# Mainboard_MCU_Func.net
KiCad netlist of a schematic drawn in Altium Designer
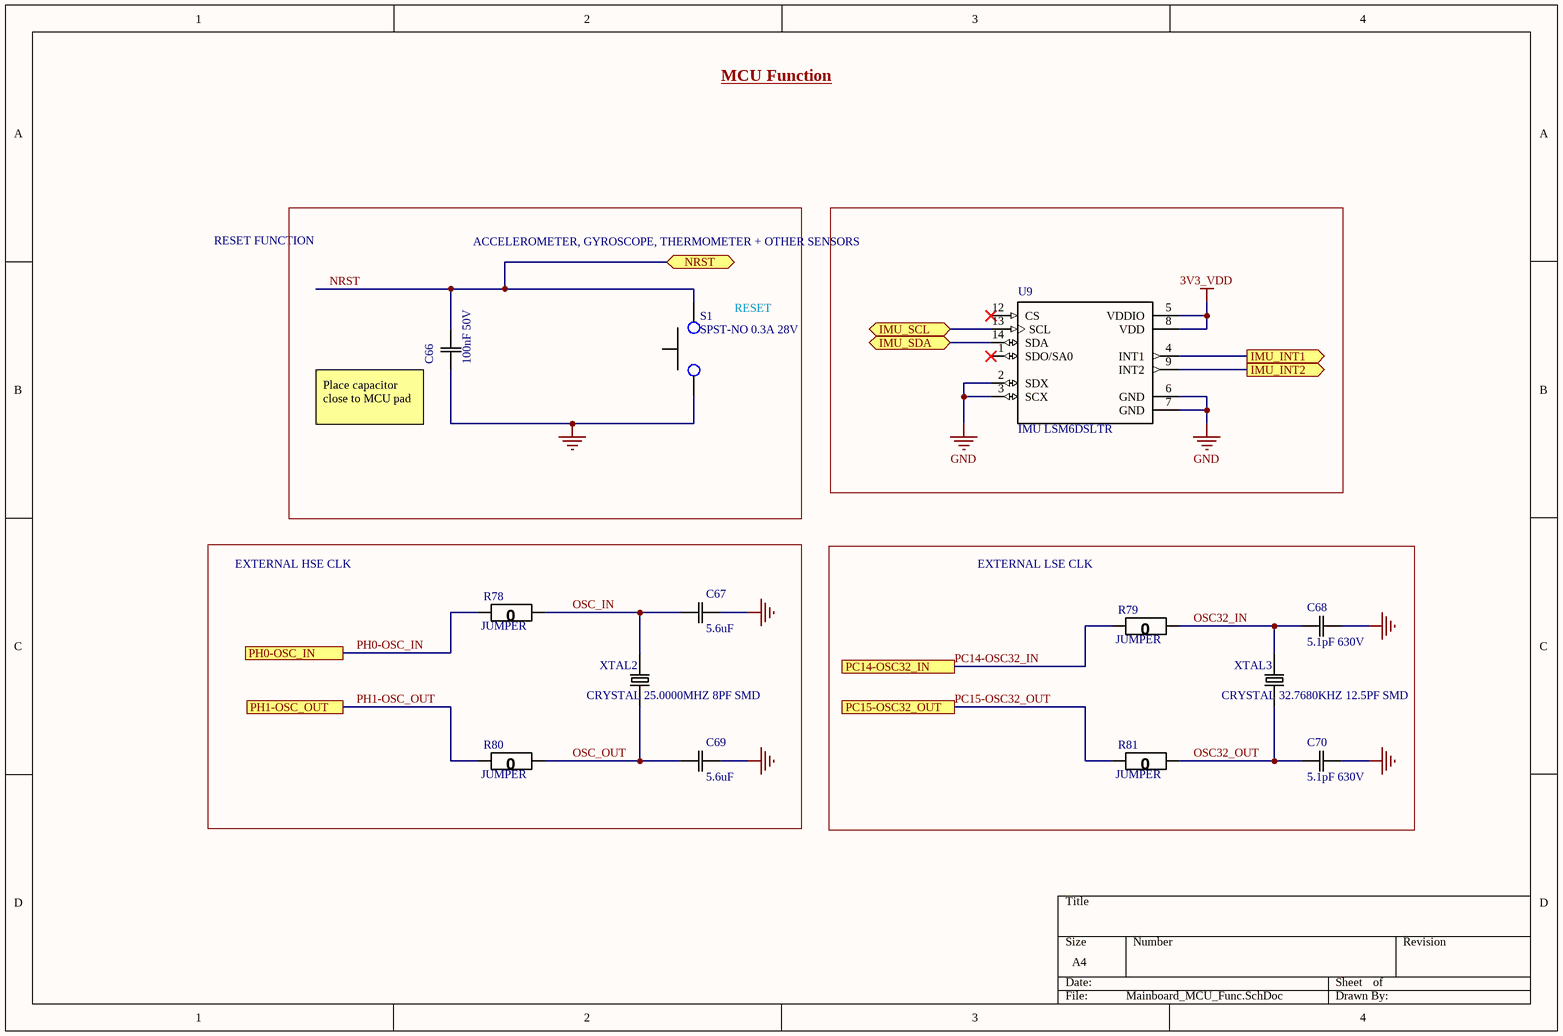
[diagram p0: Mainboard_MCU_Func.SchDoc]

(export (version "E")
  (design (tool "Eeschema 10.0.6"))
  (components
    (comp (ref "C66")
      (value "100nF 50V")
      (footprint "0805")
      (description "CAP CER 0.1UF 50V X7R 0805")
      (fields (field (name "TOLERANCE") "10%"))
      (libsource (lib "AltiumLibraries") (part "CAP 100nF 50V"))
    )
    (comp (ref "C67")
      (value "5.6uF")
      (footprint "0805")
      (description "CAP CER 5.6UF 6.3V X5R 0805")
      (fields (field (name "TOLERANCE") "10%"))
      (libsource (lib "AltiumLibraries") (part "CAP 5.6uF 6.3V"))
    )
    (comp (ref "C68")
      (value "5.1pF 630V")
      (footprint "0805")
      (description "CAP CER 5.1PF 630V C0G/NP0 0805")
      (fields (field (name "TOLERANCE") "10%"))
      (libsource (lib "AltiumLibraries") (part "CAP 5.1pF 630V"))
    )
    (comp (ref "C69")
      (value "5.6uF")
      (footprint "0805")
      (description "CAP CER 5.6UF 6.3V X5R 0805")
      (fields (field (name "TOLERANCE") "10%"))
      (libsource (lib "AltiumLibraries") (part "CAP 5.6uF 6.3V"))
    )
    (comp (ref "C70")
      (value "5.1pF 630V")
      (footprint "0805")
      (description "CAP CER 5.1PF 630V C0G/NP0 0805")
      (fields (field (name "TOLERANCE") "10%"))
      (libsource (lib "AltiumLibraries") (part "CAP 5.1pF 630V"))
    )
    (comp (ref "R78")
      (value "JUMPER")
      (footprint "0805")
      (description "RES SMD 0 OHM JUMPER GENERIC 0805")
      (libsource (lib "AltiumLibraries") (part "RES 0 JUMPER"))
    )
    (comp (ref "R79")
      (value "JUMPER")
      (footprint "0805")
      (description "RES SMD 0 OHM JUMPER GENERIC 0805")
      (libsource (lib "AltiumLibraries") (part "RES 0 JUMPER"))
    )
    (comp (ref "R80")
      (value "JUMPER")
      (footprint "0805")
      (description "RES SMD 0 OHM JUMPER GENERIC 0805")
      (libsource (lib "AltiumLibraries") (part "RES 0 JUMPER"))
    )
    (comp (ref "R81")
      (value "JUMPER")
      (footprint "0805")
      (description "RES SMD 0 OHM JUMPER GENERIC 0805")
      (libsource (lib "AltiumLibraries") (part "RES 0 JUMPER"))
    )
    (comp (ref "S1")
      (value "SPST-NO 0.3A 28V")
      (footprint "PB300STQ")
      (description "Pushbutton Switch SPST-NO Standard Through Hole")
      (fields (field (name "MF") "E-Switch") (field (name "MP") "PB300STQ"))
      (libsource (lib "AltiumLibraries") (part "SW PUSH NO"))
    )
    (comp (ref "U9")
      (value "IMU LSM6DSLTR")
      (footprint "LGA-14")
      (description "IMU ACCEL/GYRO I2C/SPI 14LGA")
      (fields (field (name "MP") "LSM6DSLTR") (field (name "MF") "STMicroelectronics"))
      (libsource (lib "AltiumLibraries") (part "IMU LSM6DSLTR"))
    )
    (comp (ref "XTAL2")
      (value "CRYSTAL 25.0000MHZ 8PF SMD")
      (footprint "SMD-2")
      (description "25MHz ±50ppm Crystal 8pF 70 Ohms 2-SMD, No Lead")
      (fields (field (name "MP") "NX5032GA-25.000000MHZ-LN-CD-1") (field (name "MF") "NDK America, Inc."))
      (libsource (lib "AltiumLibraries") (part "XTAL 25MHZ 8PF SMD"))
    )
    (comp (ref "XTAL3")
      (value "CRYSTAL 32.7680KHZ 12.5PF SMD")
      (footprint "SMD-2")
      (description "32.768kHz ±20ppm Crystal 12.5pF 70 kOhms 2-SMD, No Lead")
      (fields (field (name "MP") "NX3215SA-32.768K-STD-MUA-8") (field (name "MF") "NDK America, Inc."))
      (libsource (lib "AltiumLibraries") (part "XTAL 32.7680KHZ 12.5PF SMD"))
    )
  )
  (nets
    (net (code "1") (name "/IMU_INT1") (class "Default")
      (node (ref "U9") (pin "4") (pinfunction "INT1_4") (pintype "output"))
    )
    (net (code "2") (name "/IMU_INT2") (class "Default")
      (node (ref "U9") (pin "9") (pinfunction "INT2_9") (pintype "output"))
    )
    (net (code "3") (name "/IMU_SCL") (class "Default")
      (node (ref "U9") (pin "13") (pinfunction "SCL_13") (pintype "input"))
    )
    (net (code "4") (name "/IMU_SDA") (class "Default")
      (node (ref "U9") (pin "14") (pinfunction "SDA_14") (pintype "bidirectional"))
    )
    (net (code "5") (name "/NRST") (class "Default")
      (node (ref "C66") (pin "2") (pinfunction "C2_2") (pintype "passive"))
      (node (ref "S1") (pin "2") (pinfunction "2_2") (pintype "passive"))
    )
    (net (code "6") (name "/OSC32_IN") (class "Default")
      (node (ref "C68") (pin "1") (pinfunction "C1_1") (pintype "passive"))
      (node (ref "R79") (pin "1") (pinfunction "R1_1") (pintype "passive"))
      (node (ref "XTAL3") (pin "2") (pinfunction "2_2") (pintype "passive"))
    )
    (net (code "7") (name "/OSC32_OUT") (class "Default")
      (node (ref "C70") (pin "1") (pinfunction "C1_1") (pintype "passive"))
      (node (ref "R81") (pin "1") (pinfunction "R1_1") (pintype "passive"))
      (node (ref "XTAL3") (pin "1") (pinfunction "1_1") (pintype "passive"))
    )
    (net (code "8") (name "/OSC_IN") (class "Default")
      (node (ref "C67") (pin "1") (pinfunction "C1_1") (pintype "passive"))
      (node (ref "R78") (pin "1") (pinfunction "R1_1") (pintype "passive"))
      (node (ref "XTAL2") (pin "2") (pinfunction "2_2") (pintype "passive"))
    )
    (net (code "9") (name "/OSC_OUT") (class "Default")
      (node (ref "C69") (pin "1") (pinfunction "C1_1") (pintype "passive"))
      (node (ref "R80") (pin "1") (pinfunction "R1_1") (pintype "passive"))
      (node (ref "XTAL2") (pin "1") (pinfunction "1_1") (pintype "passive"))
    )
    (net (code "10") (name "/PC14-OSC32_IN") (class "Default")
      (node (ref "R79") (pin "2") (pinfunction "R2_2") (pintype "passive"))
    )
    (net (code "11") (name "/PC15-OSC32_OUT") (class "Default")
      (node (ref "R81") (pin "2") (pinfunction "R2_2") (pintype "passive"))
    )
    (net (code "12") (name "/PH0-OSC_IN") (class "Default")
      (node (ref "R78") (pin "2") (pinfunction "R2_2") (pintype "passive"))
    )
    (net (code "13") (name "/PH1-OSC_OUT") (class "Default")
      (node (ref "R80") (pin "2") (pinfunction "R2_2") (pintype "passive"))
    )
    (net (code "14") (name "3V3_VDD") (class "Default")
      (node (ref "U9") (pin "5") (pinfunction "VDDIO_5") (pintype "power_in"))
      (node (ref "U9") (pin "8") (pinfunction "VDD_8") (pintype "power_in"))
    )
    (net (code "15") (name "GND") (class "Default")
      (node (ref "C66") (pin "1") (pinfunction "C1_1") (pintype "passive"))
      (node (ref "C67") (pin "2") (pinfunction "C2_2") (pintype "passive"))
      (node (ref "C68") (pin "2") (pinfunction "C2_2") (pintype "passive"))
      (node (ref "C69") (pin "2") (pinfunction "C2_2") (pintype "passive"))
      (node (ref "C70") (pin "2") (pinfunction "C2_2") (pintype "passive"))
      (node (ref "S1") (pin "1") (pinfunction "1_1") (pintype "passive"))
      (node (ref "U9") (pin "2") (pinfunction "SDX_2") (pintype "bidirectional"))
      (node (ref "U9") (pin "3") (pinfunction "SCX_3") (pintype "bidirectional"))
      (node (ref "U9") (pin "6") (pinfunction "GND_6") (pintype "power_in"))
      (node (ref "U9") (pin "7") (pinfunction "GND_7") (pintype "power_in"))
    )
    (net (code "16") (name "unconnected-(U9-CS-Pad12)") (class "Default")
      (node (ref "U9") (pin "12") (pinfunction "CS_12") (pintype "input+no_connect"))
    )
    (net (code "17") (name "unconnected-(U9-SDO{slash}SA0-Pad1)") (class "Default")
      (node (ref "U9") (pin "1") (pinfunction "SDO/SA0_1") (pintype "bidirectional+no_connect"))
    )
  )
)
